# usbmidi.net
KiCad netlist of a schematic drawn in EAGLE
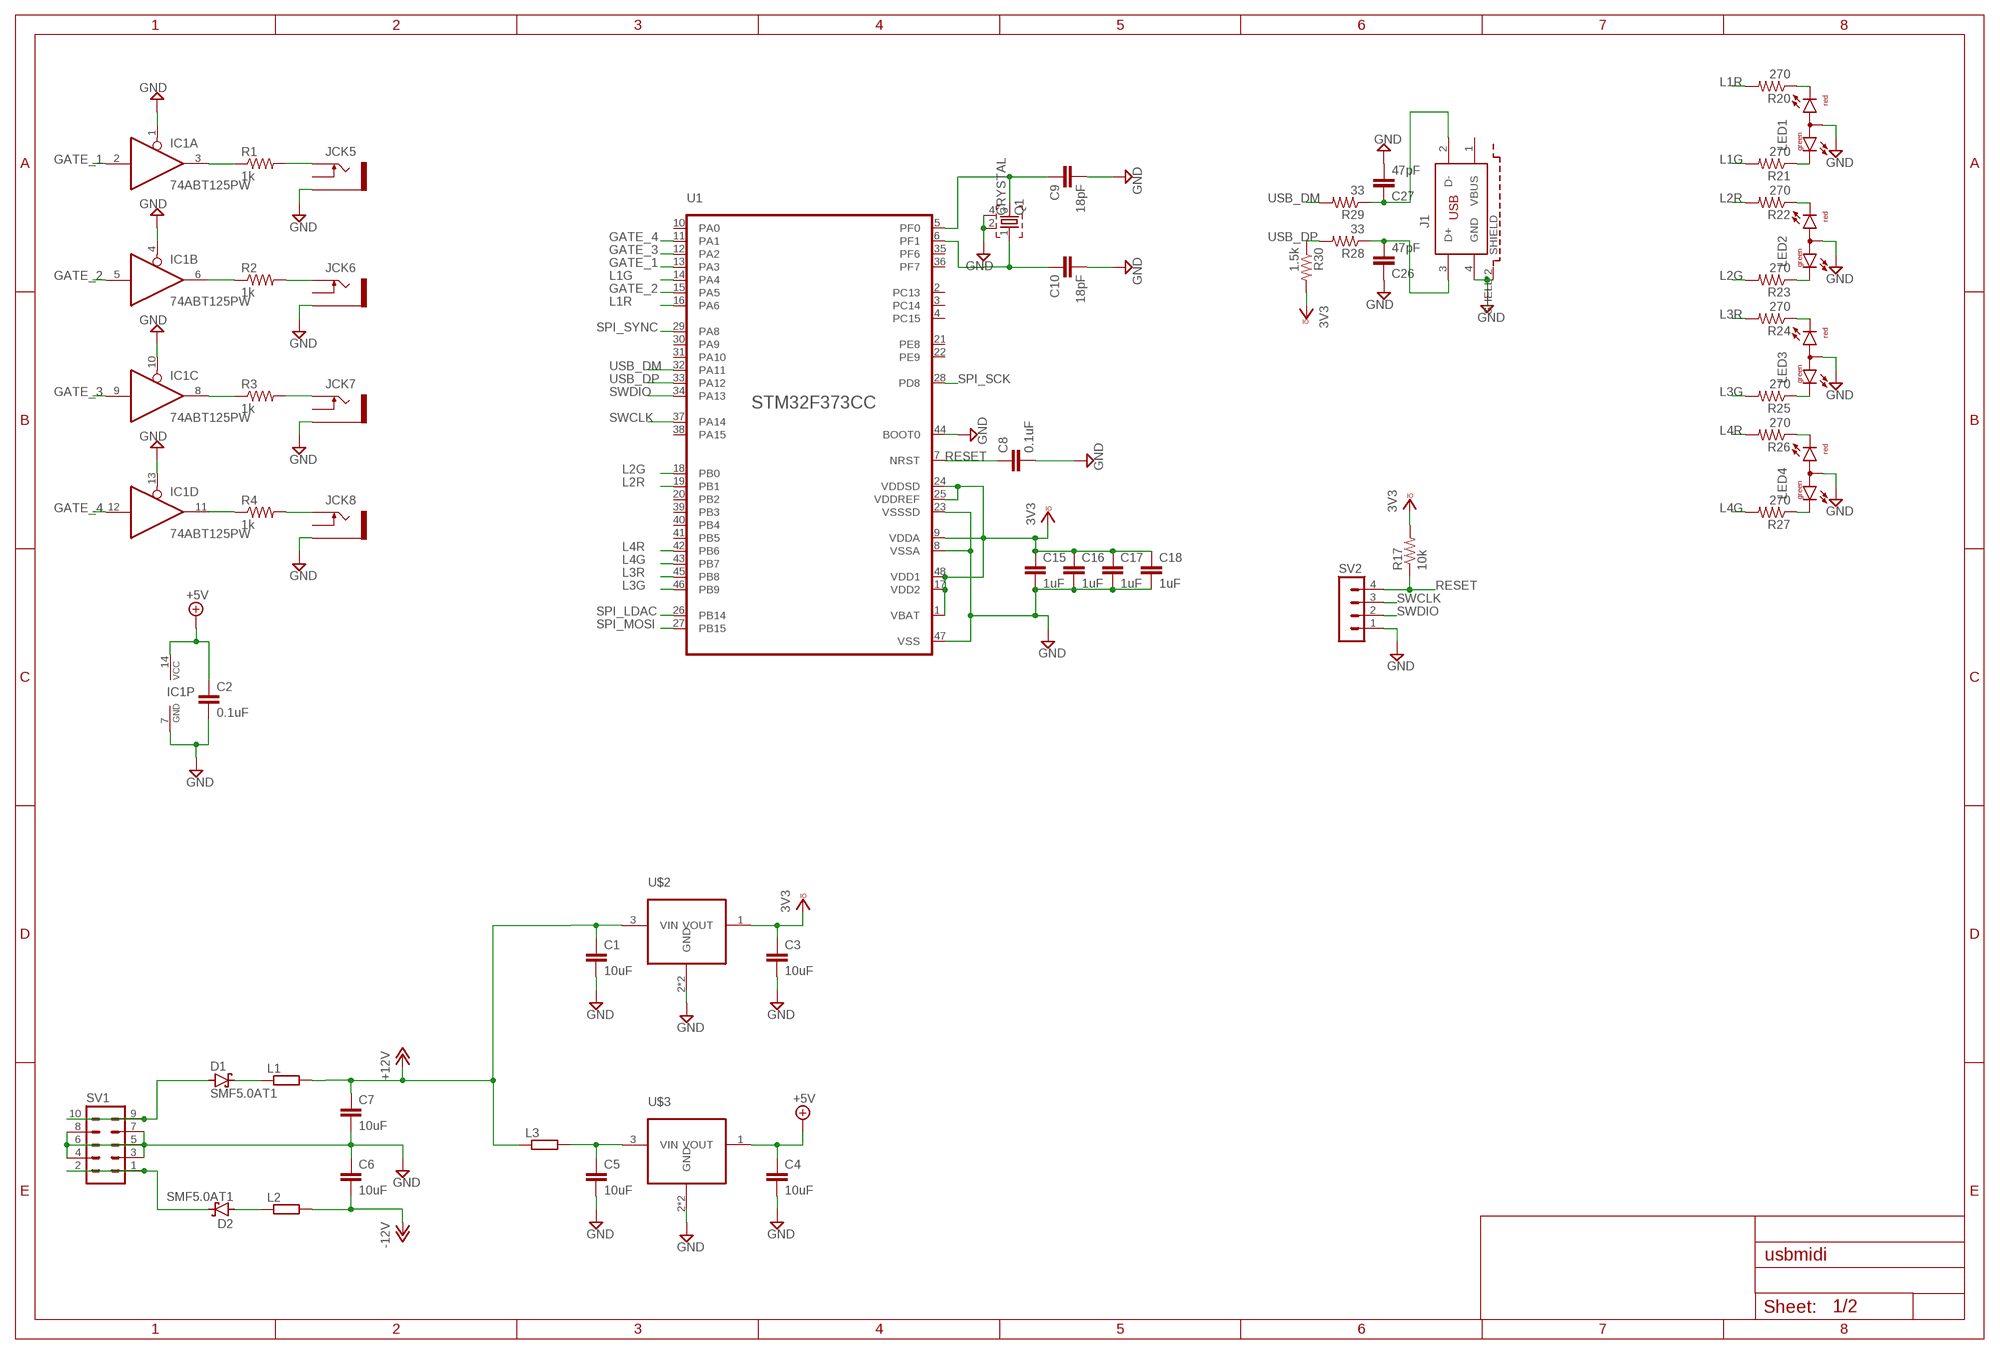
[diagram p0: schematic, sheet 1]
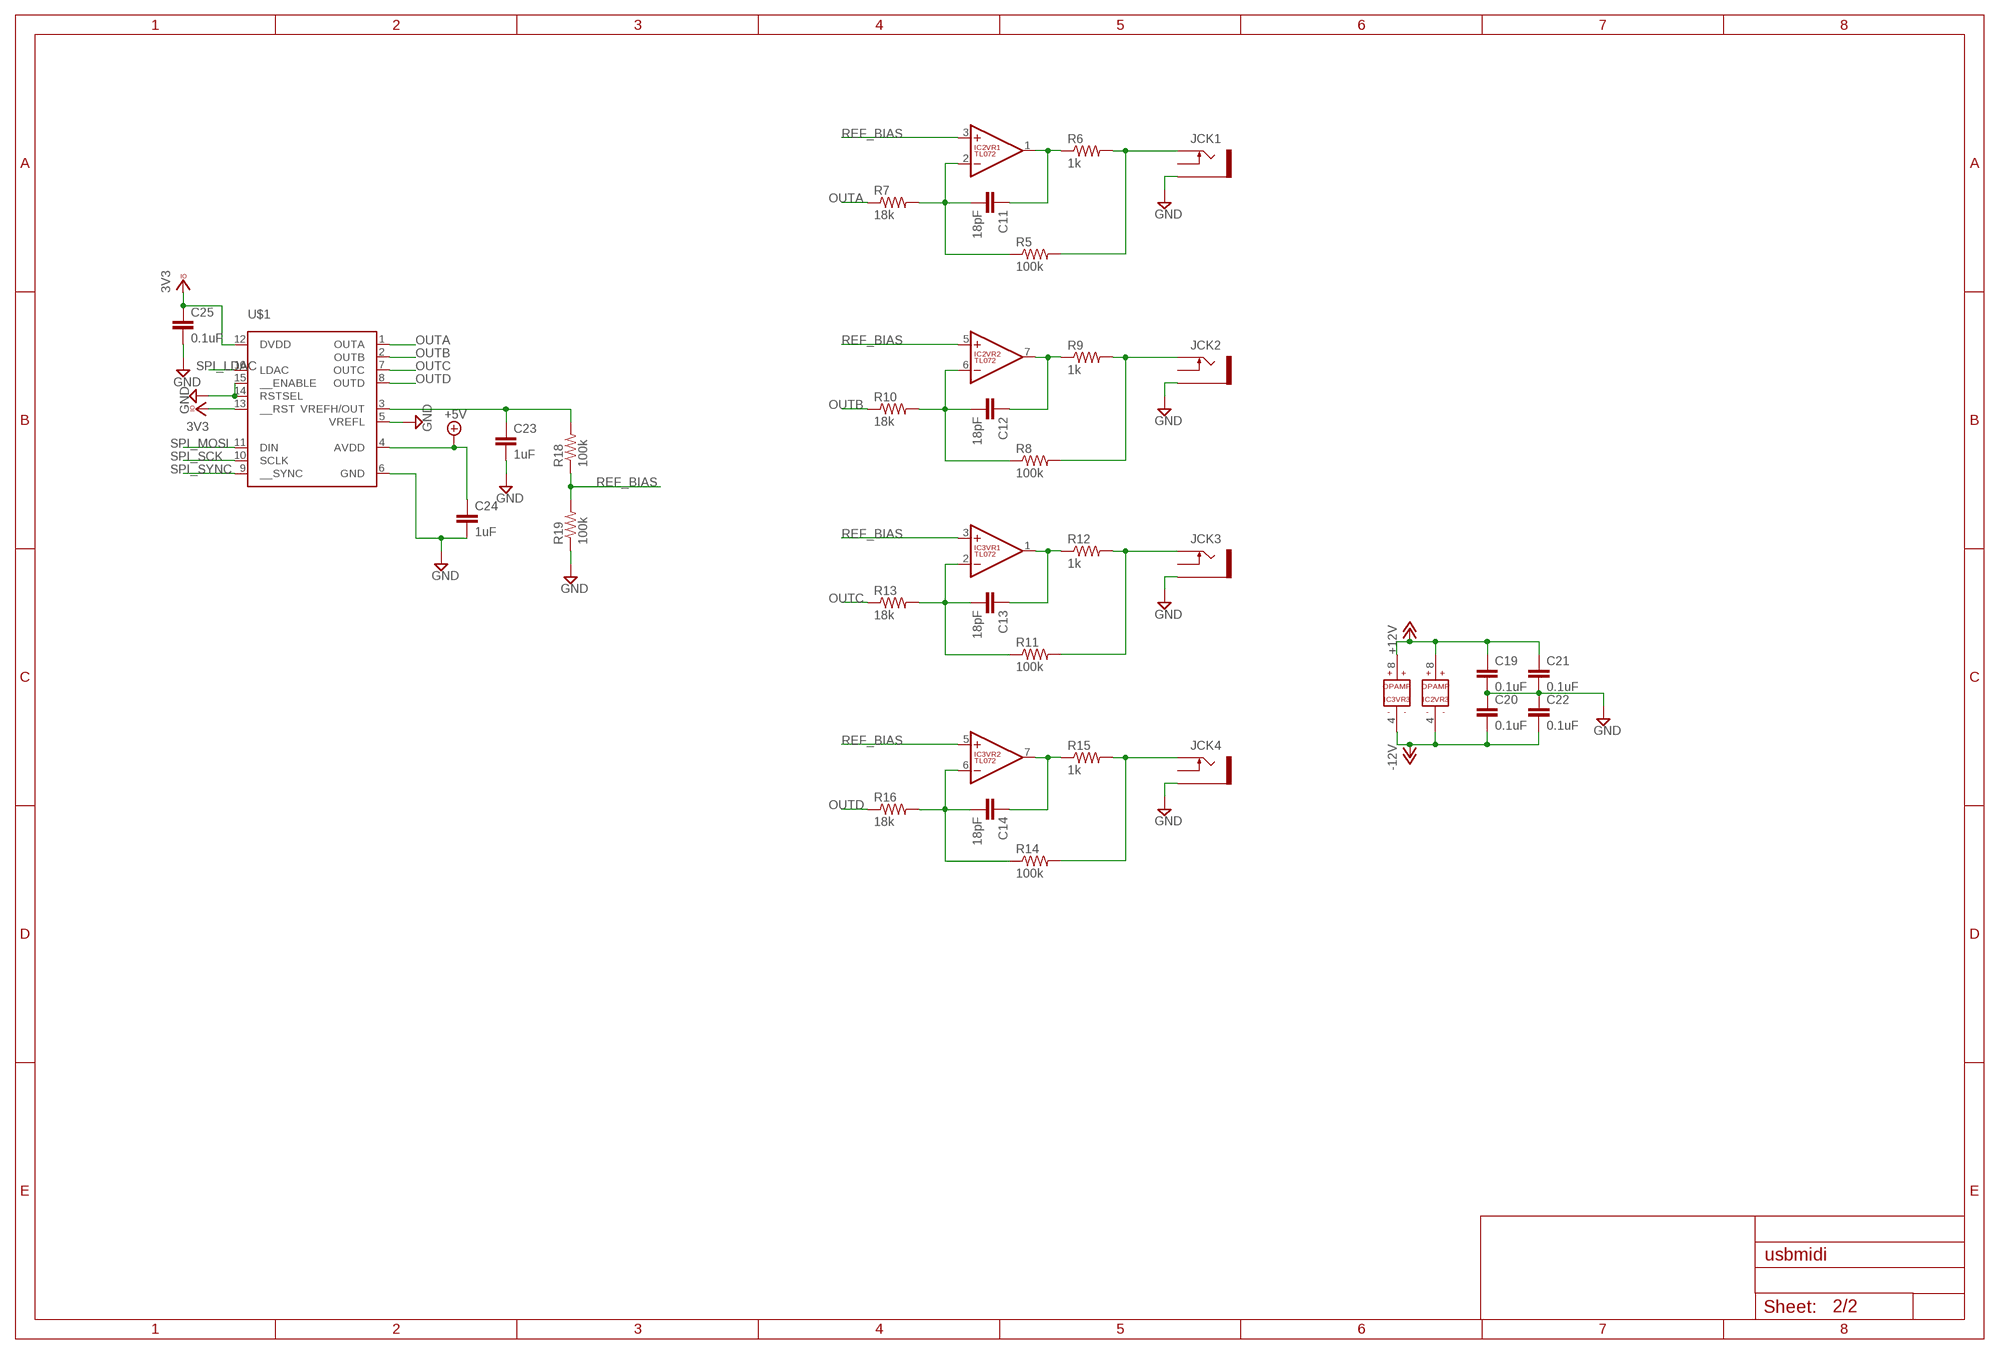
[diagram p1: schematic, sheet 2]

(export (version "E")
  (design (tool "Eeschema 10.0.6"))
  (components
    (comp (ref "C11")
      (value "18pF")
      (footprint "eagle-import:C0603K")
      (libsource (lib "eagle-import") (part "C-EUC0603K"))
    )
    (comp (ref "C12")
      (value "18pF")
      (footprint "eagle-import:C0603K")
      (libsource (lib "eagle-import") (part "C-EUC0603K"))
    )
    (comp (ref "C13")
      (value "18pF")
      (footprint "eagle-import:C0603K")
      (libsource (lib "eagle-import") (part "C-EUC0603K"))
    )
    (comp (ref "C14")
      (value "18pF")
      (footprint "eagle-import:C0603K")
      (libsource (lib "eagle-import") (part "C-EUC0603K"))
    )
    (comp (ref "C19")
      (value "0.1uF")
      (footprint "eagle-import:C0603K")
      (libsource (lib "eagle-import") (part "C-EUC0603K"))
    )
    (comp (ref "C20")
      (value "0.1uF")
      (footprint "eagle-import:C0603K")
      (libsource (lib "eagle-import") (part "C-EUC0603K"))
    )
    (comp (ref "C21")
      (value "0.1uF")
      (footprint "eagle-import:C0603K")
      (libsource (lib "eagle-import") (part "C-EUC0603K"))
    )
    (comp (ref "C22")
      (value "0.1uF")
      (footprint "eagle-import:C0603K")
      (libsource (lib "eagle-import") (part "C-EUC0603K"))
    )
    (comp (ref "C23")
      (value "1uF")
      (footprint "eagle-import:C0603K")
      (libsource (lib "eagle-import") (part "C-EUC0603K"))
    )
    (comp (ref "C24")
      (value "1uF")
      (footprint "eagle-import:C0603K")
      (libsource (lib "eagle-import") (part "C-EUC0603K"))
    )
    (comp (ref "C25")
      (value "0.1uF")
      (footprint "eagle-import:C0603K")
      (libsource (lib "eagle-import") (part "C-EUC0603K"))
    )
    (comp (ref "IC2")
      (value "TL072")
      (footprint "eagle-import:SO08")
      (libsource (lib "eagle-import") (part "TL072"))
    )
    (comp (ref "IC3")
      (value "TL072")
      (footprint "eagle-import:SO08")
      (libsource (lib "eagle-import") (part "TL072"))
    )
    (comp (ref "JCK1")
      (value "THONKICONNNEW")
      (footprint "eagle-import:WQP-PJ301M-12_JACK")
      (libsource (lib "eagle-import") (part "THONKICONNNEW"))
    )
    (comp (ref "JCK2")
      (value "THONKICONNNEW")
      (footprint "eagle-import:WQP-PJ301M-12_JACK")
      (libsource (lib "eagle-import") (part "THONKICONNNEW"))
    )
    (comp (ref "JCK3")
      (value "THONKICONNNEW")
      (footprint "eagle-import:WQP-PJ301M-12_JACK")
      (libsource (lib "eagle-import") (part "THONKICONNNEW"))
    )
    (comp (ref "JCK4")
      (value "THONKICONNNEW")
      (footprint "eagle-import:WQP-PJ301M-12_JACK")
      (libsource (lib "eagle-import") (part "THONKICONNNEW"))
    )
    (comp (ref "R5")
      (value "100k")
      (footprint "eagle-import:R0603")
      (libsource (lib "eagle-import") (part "R-US_R0603"))
    )
    (comp (ref "R6")
      (value "1k")
      (footprint "eagle-import:R0603")
      (libsource (lib "eagle-import") (part "R-US_R0603"))
    )
    (comp (ref "R7")
      (value "18k")
      (footprint "eagle-import:R0603")
      (libsource (lib "eagle-import") (part "R-US_R0603"))
    )
    (comp (ref "R8")
      (value "100k")
      (footprint "eagle-import:R0603")
      (libsource (lib "eagle-import") (part "R-US_R0603"))
    )
    (comp (ref "R9")
      (value "1k")
      (footprint "eagle-import:R0603")
      (libsource (lib "eagle-import") (part "R-US_R0603"))
    )
    (comp (ref "R10")
      (value "18k")
      (footprint "eagle-import:R0603")
      (libsource (lib "eagle-import") (part "R-US_R0603"))
    )
    (comp (ref "R11")
      (value "100k")
      (footprint "eagle-import:R0603")
      (libsource (lib "eagle-import") (part "R-US_R0603"))
    )
    (comp (ref "R12")
      (value "1k")
      (footprint "eagle-import:R0603")
      (libsource (lib "eagle-import") (part "R-US_R0603"))
    )
    (comp (ref "R13")
      (value "18k")
      (footprint "eagle-import:R0603")
      (libsource (lib "eagle-import") (part "R-US_R0603"))
    )
    (comp (ref "R14")
      (value "100k")
      (footprint "eagle-import:R0603")
      (libsource (lib "eagle-import") (part "R-US_R0603"))
    )
    (comp (ref "R15")
      (value "1k")
      (footprint "eagle-import:R0603")
      (libsource (lib "eagle-import") (part "R-US_R0603"))
    )
    (comp (ref "R16")
      (value "18k")
      (footprint "eagle-import:R0603")
      (libsource (lib "eagle-import") (part "R-US_R0603"))
    )
    (comp (ref "R18")
      (value "100k")
      (footprint "eagle-import:R0603")
      (libsource (lib "eagle-import") (part "R-US_R0603"))
    )
    (comp (ref "R19")
      (value "100k")
      (footprint "eagle-import:R0603")
      (libsource (lib "eagle-import") (part "R-US_R0603"))
    )
    (comp (ref "U$1")
      (value "DAC8565")
      (footprint "eagle-import:TSSOP16")
      (libsource (lib "eagle-import") (part "DAC8565"))
    )
    (comp (ref "C1")
      (value "10uF")
      (footprint "eagle-import:C0805")
      (libsource (lib "eagle-import") (part "C-EUC0805"))
    )
    (comp (ref "C2")
      (value "0.1uF")
      (footprint "eagle-import:C0603K")
      (libsource (lib "eagle-import") (part "C-EUC0603K"))
    )
    (comp (ref "C3")
      (value "10uF")
      (footprint "eagle-import:C0805")
      (libsource (lib "eagle-import") (part "C-EUC0805"))
    )
    (comp (ref "C4")
      (value "10uF")
      (footprint "eagle-import:C0805")
      (libsource (lib "eagle-import") (part "C-EUC0805"))
    )
    (comp (ref "C5")
      (value "10uF")
      (footprint "eagle-import:C0805")
      (libsource (lib "eagle-import") (part "C-EUC0805"))
    )
    (comp (ref "C6")
      (value "10uF")
      (footprint "eagle-import:C0805")
      (libsource (lib "eagle-import") (part "C-EUC0805"))
    )
    (comp (ref "C7")
      (value "10uF")
      (footprint "eagle-import:C0805")
      (libsource (lib "eagle-import") (part "C-EUC0805"))
    )
    (comp (ref "C8")
      (value "0.1uF")
      (footprint "eagle-import:C0603K")
      (libsource (lib "eagle-import") (part "C-EUC0603K"))
    )
    (comp (ref "C9")
      (value "18pF")
      (footprint "eagle-import:C0603K")
      (libsource (lib "eagle-import") (part "C-EUC0603K"))
    )
    (comp (ref "C10")
      (value "18pF")
      (footprint "eagle-import:C0603K")
      (libsource (lib "eagle-import") (part "C-EUC0603K"))
    )
    (comp (ref "C15")
      (value "1uF")
      (footprint "eagle-import:C0603K")
      (libsource (lib "eagle-import") (part "C-EUC0603K"))
    )
    (comp (ref "C16")
      (value "1uF")
      (footprint "eagle-import:C0603K")
      (libsource (lib "eagle-import") (part "C-EUC0603K"))
    )
    (comp (ref "C17")
      (value "1uF")
      (footprint "eagle-import:C0603K")
      (libsource (lib "eagle-import") (part "C-EUC0603K"))
    )
    (comp (ref "C18")
      (value "1uF")
      (footprint "eagle-import:C0603K")
      (libsource (lib "eagle-import") (part "C-EUC0603K"))
    )
    (comp (ref "C26")
      (value "47pF")
      (footprint "eagle-import:C0603K")
      (libsource (lib "eagle-import") (part "C-EUC0603K"))
    )
    (comp (ref "C27")
      (value "47pF")
      (footprint "eagle-import:C0603K")
      (libsource (lib "eagle-import") (part "C-EUC0603K"))
    )
    (comp (ref "D1")
      (value "SMF5.0AT1")
      (footprint "eagle-import:SOD123FL")
      (libsource (lib "eagle-import") (part "SMF5.0AT1"))
    )
    (comp (ref "D2")
      (value "SMF5.0AT1")
      (footprint "eagle-import:SOD123FL")
      (libsource (lib "eagle-import") (part "SMF5.0AT1"))
    )
    (comp (ref "IC1")
      (value "74ABT125PW")
      (footprint "eagle-import:TSSOP14")
      (libsource (lib "eagle-import") (part "74125PWABT"))
    )
    (comp (ref "J1")
      (value "61400413321")
      (footprint "eagle-import:61400413321")
      (libsource (lib "eagle-import") (part "61400413321"))
    )
    (comp (ref "JCK5")
      (value "THONKICONNNEW")
      (footprint "eagle-import:WQP-PJ301M-12_JACK")
      (libsource (lib "eagle-import") (part "THONKICONNNEW"))
    )
    (comp (ref "JCK6")
      (value "THONKICONNNEW")
      (footprint "eagle-import:WQP-PJ301M-12_JACK")
      (libsource (lib "eagle-import") (part "THONKICONNNEW"))
    )
    (comp (ref "JCK7")
      (value "THONKICONNNEW")
      (footprint "eagle-import:WQP-PJ301M-12_JACK")
      (libsource (lib "eagle-import") (part "THONKICONNNEW"))
    )
    (comp (ref "JCK8")
      (value "THONKICONNNEW")
      (footprint "eagle-import:WQP-PJ301M-12_JACK")
      (libsource (lib "eagle-import") (part "THONKICONNNEW"))
    )
    (comp (ref "L1")
      (value "R-EU_R0603")
      (footprint "eagle-import:R0603")
      (libsource (lib "eagle-import") (part "R-EU_R0603"))
    )
    (comp (ref "L2")
      (value "R-EU_R0603")
      (footprint "eagle-import:R0603")
      (libsource (lib "eagle-import") (part "R-EU_R0603"))
    )
    (comp (ref "L3")
      (value "R-EU_R0603")
      (footprint "eagle-import:R0603")
      (libsource (lib "eagle-import") (part "R-EU_R0603"))
    )
    (comp (ref "LED1")
      (value "L-115WEGW-CA")
      (footprint "eagle-import:DUOLED-A-3MM")
      (libsource (lib "eagle-import") (part "L-115WEGW-CA"))
    )
    (comp (ref "LED2")
      (value "L-115WEGW-CA")
      (footprint "eagle-import:DUOLED-A-3MM")
      (libsource (lib "eagle-import") (part "L-115WEGW-CA"))
    )
    (comp (ref "LED3")
      (value "L-115WEGW-CA")
      (footprint "eagle-import:DUOLED-A-3MM")
      (libsource (lib "eagle-import") (part "L-115WEGW-CA"))
    )
    (comp (ref "LED4")
      (value "L-115WEGW-CA")
      (footprint "eagle-import:DUOLED-A-3MM")
      (libsource (lib "eagle-import") (part "L-115WEGW-CA"))
    )
    (comp (ref "Q1")
      (value "CRYSTAL")
      (footprint "eagle-import:CTS406")
      (libsource (lib "eagle-import") (part "CRYSTAL"))
    )
    (comp (ref "R1")
      (value "1k")
      (footprint "eagle-import:R0603")
      (libsource (lib "eagle-import") (part "R-US_R0603"))
    )
    (comp (ref "R2")
      (value "1k")
      (footprint "eagle-import:R0603")
      (libsource (lib "eagle-import") (part "R-US_R0603"))
    )
    (comp (ref "R3")
      (value "1k")
      (footprint "eagle-import:R0603")
      (libsource (lib "eagle-import") (part "R-US_R0603"))
    )
    (comp (ref "R4")
      (value "1k")
      (footprint "eagle-import:R0603")
      (libsource (lib "eagle-import") (part "R-US_R0603"))
    )
    (comp (ref "R17")
      (value "10k")
      (footprint "eagle-import:R0603")
      (libsource (lib "eagle-import") (part "R-US_R0603"))
    )
    (comp (ref "R20")
      (value "270")
      (footprint "eagle-import:R0603")
      (libsource (lib "eagle-import") (part "R-US_R0603"))
    )
    (comp (ref "R21")
      (value "270")
      (footprint "eagle-import:R0603")
      (libsource (lib "eagle-import") (part "R-US_R0603"))
    )
    (comp (ref "R22")
      (value "270")
      (footprint "eagle-import:R0603")
      (libsource (lib "eagle-import") (part "R-US_R0603"))
    )
    (comp (ref "R23")
      (value "270")
      (footprint "eagle-import:R0603")
      (libsource (lib "eagle-import") (part "R-US_R0603"))
    )
    (comp (ref "R24")
      (value "270")
      (footprint "eagle-import:R0603")
      (libsource (lib "eagle-import") (part "R-US_R0603"))
    )
    (comp (ref "R25")
      (value "270")
      (footprint "eagle-import:R0603")
      (libsource (lib "eagle-import") (part "R-US_R0603"))
    )
    (comp (ref "R26")
      (value "270")
      (footprint "eagle-import:R0603")
      (libsource (lib "eagle-import") (part "R-US_R0603"))
    )
    (comp (ref "R27")
      (value "270")
      (footprint "eagle-import:R0603")
      (libsource (lib "eagle-import") (part "R-US_R0603"))
    )
    (comp (ref "R28")
      (value "33")
      (footprint "eagle-import:R0603")
      (libsource (lib "eagle-import") (part "R-US_R0603"))
    )
    (comp (ref "R29")
      (value "33")
      (footprint "eagle-import:R0603")
      (libsource (lib "eagle-import") (part "R-US_R0603"))
    )
    (comp (ref "R30")
      (value "1.5k")
      (footprint "eagle-import:R0603")
      (libsource (lib "eagle-import") (part "R-US_R0603"))
    )
    (comp (ref "SV1")
      (value "MA05-2")
      (footprint "eagle-import:MA05-2")
      (libsource (lib "eagle-import") (part "MA05-2"))
    )
    (comp (ref "SV2")
      (value "MA04-1")
      (footprint "eagle-import:MA04-1")
      (libsource (lib "eagle-import") (part "MA04-1"))
    )
    (comp (ref "U$2")
      (value "LD2981ABUSOT89")
      (footprint "eagle-import:SOT89")
      (libsource (lib "eagle-import") (part "LD2981ABUSOT89"))
    )
    (comp (ref "U$3")
      (value "LD2981ABUSOT89")
      (footprint "eagle-import:SOT89")
      (libsource (lib "eagle-import") (part "LD2981ABUSOT89"))
    )
    (comp (ref "U1")
      (value "STM32F373LQFP48")
      (footprint "eagle-import:LQFP48")
      (libsource (lib "eagle-import") (part "STM32F373LQFP48"))
    )
  )
  (nets
    (net (code "1") (name "+5V") (class "Default")
      (node (ref "C2") (pin "1") (pinfunction "1_1") (pintype "passive"))
      (node (ref "C24") (pin "1") (pinfunction "1_1") (pintype "passive"))
      (node (ref "C4") (pin "1") (pinfunction "1_1") (pintype "passive"))
      (node (ref "IC1") (pin "14") (pinfunction "VCC_14") (pintype "power_in"))
      (node (ref "U$1") (pin "4") (pinfunction "AVDD_4") (pintype "bidirectional"))
      (node (ref "U$3") (pin "1") (pinfunction "VOUT_1") (pintype "bidirectional"))
    )
    (net (code "2") (name "+12V") (class "Default")
      (node (ref "C1") (pin "1") (pinfunction "1_1") (pintype "passive"))
      (node (ref "C19") (pin "1") (pinfunction "1_1") (pintype "passive"))
      (node (ref "C21") (pin "1") (pinfunction "1_1") (pintype "passive"))
      (node (ref "C7") (pin "1") (pinfunction "1_1") (pintype "passive"))
      (node (ref "IC2") (pin "8") (pinfunction "V+_8") (pintype "power_in"))
      (node (ref "IC3") (pin "8") (pinfunction "V+_8") (pintype "power_in"))
      (node (ref "L1") (pin "2") (pinfunction "2_2") (pintype "passive"))
      (node (ref "L3") (pin "1") (pinfunction "1_1") (pintype "passive"))
      (node (ref "U$2") (pin "3") (pinfunction "VIN_3") (pintype "bidirectional"))
    )
    (net (code "3") (name "-12V") (class "Default")
      (node (ref "C20") (pin "2") (pinfunction "2_2") (pintype "passive"))
      (node (ref "C22") (pin "2") (pinfunction "2_2") (pintype "passive"))
      (node (ref "C6") (pin "2") (pinfunction "2_2") (pintype "passive"))
      (node (ref "IC2") (pin "4") (pinfunction "V-_4") (pintype "power_in"))
      (node (ref "IC3") (pin "4") (pinfunction "V-_4") (pintype "power_in"))
      (node (ref "L2") (pin "2") (pinfunction "2_2") (pintype "passive"))
    )
    (net (code "4") (name "GATE_1") (class "Default")
      (node (ref "IC1") (pin "2") (pinfunction "I_2") (pintype "input"))
      (node (ref "U1") (pin "13") (pinfunction "PA3_13") (pintype "bidirectional"))
    )
    (net (code "5") (name "GATE_2") (class "Default")
      (node (ref "IC1") (pin "5") (pinfunction "I_5") (pintype "input"))
      (node (ref "U1") (pin "15") (pinfunction "PA5_15") (pintype "bidirectional"))
    )
    (net (code "6") (name "GATE_3") (class "Default")
      (node (ref "IC1") (pin "9") (pinfunction "I_9") (pintype "input"))
      (node (ref "U1") (pin "12") (pinfunction "PA2_12") (pintype "bidirectional"))
    )
    (net (code "7") (name "GATE_4") (class "Default")
      (node (ref "IC1") (pin "12") (pinfunction "I_12") (pintype "input"))
      (node (ref "U1") (pin "11") (pinfunction "PA1_11") (pintype "bidirectional"))
    )
    (net (code "8") (name "GND") (class "Default")
      (node (ref "C1") (pin "2") (pinfunction "2_2") (pintype "passive"))
      (node (ref "C10") (pin "2") (pinfunction "2_2") (pintype "passive"))
      (node (ref "C15") (pin "2") (pinfunction "2_2") (pintype "passive"))
      (node (ref "C16") (pin "2") (pinfunction "2_2") (pintype "passive"))
      (node (ref "C17") (pin "2") (pinfunction "2_2") (pintype "passive"))
      (node (ref "C18") (pin "2") (pinfunction "2_2") (pintype "passive"))
      (node (ref "C19") (pin "2") (pinfunction "2_2") (pintype "passive"))
      (node (ref "C2") (pin "2") (pinfunction "2_2") (pintype "passive"))
      (node (ref "C20") (pin "1") (pinfunction "1_1") (pintype "passive"))
      (node (ref "C21") (pin "2") (pinfunction "2_2") (pintype "passive"))
      (node (ref "C22") (pin "1") (pinfunction "1_1") (pintype "passive"))
      (node (ref "C23") (pin "2") (pinfunction "2_2") (pintype "passive"))
      (node (ref "C24") (pin "2") (pinfunction "2_2") (pintype "passive"))
      (node (ref "C25") (pin "2") (pinfunction "2_2") (pintype "passive"))
      (node (ref "C26") (pin "1") (pinfunction "1_1") (pintype "passive"))
      (node (ref "C27") (pin "2") (pinfunction "2_2") (pintype "passive"))
      (node (ref "C3") (pin "2") (pinfunction "2_2") (pintype "passive"))
      (node (ref "C4") (pin "2") (pinfunction "2_2") (pintype "passive"))
      (node (ref "C5") (pin "2") (pinfunction "2_2") (pintype "passive"))
      (node (ref "C6") (pin "1") (pinfunction "1_1") (pintype "passive"))
      (node (ref "C7") (pin "2") (pinfunction "2_2") (pintype "passive"))
      (node (ref "C8") (pin "2") (pinfunction "2_2") (pintype "passive"))
      (node (ref "C9") (pin "2") (pinfunction "2_2") (pintype "passive"))
      (node (ref "IC1") (pin "1") (pinfunction "OE_1") (pintype "input"))
      (node (ref "IC1") (pin "10") (pinfunction "OE_10") (pintype "input"))
      (node (ref "IC1") (pin "13") (pinfunction "OE_13") (pintype "input"))
      (node (ref "IC1") (pin "4") (pinfunction "OE_4") (pintype "input"))
      (node (ref "IC1") (pin "7") (pinfunction "GND_7") (pintype "power_in"))
      (node (ref "J1") (pin "4") (pinfunction "GND_4") (pintype "bidirectional"))
      (node (ref "J1") (pin "SHELL") (pinfunction "SHIELD_SHELL") (pintype "bidirectional"))
      (node (ref "J1") (pin "SHELL1") (pinfunction "SHIELD_SHELL1") (pintype "bidirectional"))
      (node (ref "JCK1") (pin "P$3_SLEEVE") (pinfunction "SLEEVE_P$3_SLEEVE") (pintype "passive"))
      (node (ref "JCK2") (pin "P$3_SLEEVE") (pinfunction "SLEEVE_P$3_SLEEVE") (pintype "passive"))
      (node (ref "JCK3") (pin "P$3_SLEEVE") (pinfunction "SLEEVE_P$3_SLEEVE") (pintype "passive"))
      (node (ref "JCK4") (pin "P$3_SLEEVE") (pinfunction "SLEEVE_P$3_SLEEVE") (pintype "passive"))
      (node (ref "JCK5") (pin "P$3_SLEEVE") (pinfunction "SLEEVE_P$3_SLEEVE") (pintype "passive"))
      (node (ref "JCK6") (pin "P$3_SLEEVE") (pinfunction "SLEEVE_P$3_SLEEVE") (pintype "passive"))
      (node (ref "JCK7") (pin "P$3_SLEEVE") (pinfunction "SLEEVE_P$3_SLEEVE") (pintype "passive"))
      (node (ref "JCK8") (pin "P$3_SLEEVE") (pinfunction "SLEEVE_P$3_SLEEVE") (pintype "passive"))
      (node (ref "LED1") (pin "2") (pinfunction "A_2") (pintype "passive"))
      (node (ref "LED2") (pin "2") (pinfunction "A_2") (pintype "passive"))
      (node (ref "LED3") (pin "2") (pinfunction "A_2") (pintype "passive"))
      (node (ref "LED4") (pin "2") (pinfunction "A_2") (pintype "passive"))
      (node (ref "Q1") (pin "2") (pinfunction "2_2") (pintype "passive"))
      (node (ref "Q1") (pin "4") (pinfunction "4_4") (pintype "passive"))
      (node (ref "R19") (pin "1") (pinfunction "1_1") (pintype "passive"))
      (node (ref "SV1") (pin "3") (pinfunction "3_3") (pintype "passive"))
      (node (ref "SV1") (pin "4") (pinfunction "4_4") (pintype "passive"))
      (node (ref "SV1") (pin "5") (pinfunction "5_5") (pintype "passive"))
      (node (ref "SV1") (pin "6") (pinfunction "6_6") (pintype "passive"))
      (node (ref "SV1") (pin "7") (pinfunction "7_7") (pintype "passive"))
      (node (ref "SV1") (pin "8") (pinfunction "8_8") (pintype "passive"))
      (node (ref "SV2") (pin "1") (pinfunction "1_1") (pintype "passive"))
      (node (ref "U$1") (pin "14") (pinfunction "RSTSEL_14") (pintype "bidirectional"))
      (node (ref "U$1") (pin "15") (pinfunction "__ENABLE_15") (pintype "bidirectional"))
      (node (ref "U$1") (pin "5") (pinfunction "VREFL_5") (pintype "bidirectional"))
      (node (ref "U$1") (pin "6") (pinfunction "GND_6") (pintype "bidirectional"))
      (node (ref "U$2") (pin "2") (pinfunction "GND_2") (pintype "bidirectional"))
      (node (ref "U$2") (pin "2@1") (pinfunction "GND_2@1") (pintype "bidirectional"))
      (node (ref "U$3") (pin "2") (pinfunction "GND_2") (pintype "bidirectional"))
      (node (ref "U$3") (pin "2@1") (pinfunction "GND_2@1") (pintype "bidirectional"))
      (node (ref "U1") (pin "23") (pinfunction "VSSSD_23") (pintype "bidirectional"))
      (node (ref "U1") (pin "44") (pinfunction "BOOT0_44") (pintype "bidirectional"))
      (node (ref "U1") (pin "47") (pinfunction "VSS_47") (pintype "bidirectional"))
      (node (ref "U1") (pin "8") (pinfunction "VSSA_8") (pintype "bidirectional"))
    )
    (net (code "9") (name "L1G") (class "Default")
      (node (ref "R21") (pin "2") (pinfunction "2_2") (pintype "passive"))
      (node (ref "U1") (pin "14") (pinfunction "PA4_14") (pintype "bidirectional"))
    )
    (net (code "10") (name "L1R") (class "Default")
      (node (ref "R20") (pin "2") (pinfunction "2_2") (pintype "passive"))
      (node (ref "U1") (pin "16") (pinfunction "PA6_16") (pintype "bidirectional"))
    )
    (net (code "11") (name "L2G") (class "Default")
      (node (ref "R23") (pin "2") (pinfunction "2_2") (pintype "passive"))
      (node (ref "U1") (pin "18") (pinfunction "PB0_18") (pintype "bidirectional"))
    )
    (net (code "12") (name "L2R") (class "Default")
      (node (ref "R22") (pin "2") (pinfunction "2_2") (pintype "passive"))
      (node (ref "U1") (pin "19") (pinfunction "PB1_19") (pintype "bidirectional"))
    )
    (net (code "13") (name "L3G") (class "Default")
      (node (ref "R25") (pin "2") (pinfunction "2_2") (pintype "passive"))
      (node (ref "U1") (pin "46") (pinfunction "PB9_46") (pintype "bidirectional"))
    )
    (net (code "14") (name "L3R") (class "Default")
      (node (ref "R24") (pin "2") (pinfunction "2_2") (pintype "passive"))
      (node (ref "U1") (pin "45") (pinfunction "PB8_45") (pintype "bidirectional"))
    )
    (net (code "15") (name "L4G") (class "Default")
      (node (ref "R27") (pin "2") (pinfunction "2_2") (pintype "passive"))
      (node (ref "U1") (pin "43") (pinfunction "PB7_43") (pintype "bidirectional"))
    )
    (net (code "16") (name "L4R") (class "Default")
      (node (ref "R26") (pin "2") (pinfunction "2_2") (pintype "passive"))
      (node (ref "U1") (pin "42") (pinfunction "PB6_42") (pintype "bidirectional"))
    )
    (net (code "17") (name "Net-(D1-PadA)") (class "Default")
      (node (ref "D1") (pin "A") (pinfunction "A_A") (pintype "passive"))
      (node (ref "SV1") (pin "10") (pinfunction "10_10") (pintype "passive"))
      (node (ref "SV1") (pin "9") (pinfunction "9_9") (pintype "passive"))
    )
    (net (code "18") (name "Net-(D1-PadC)") (class "Default")
      (node (ref "D1") (pin "C") (pinfunction "C_C") (pintype "passive"))
      (node (ref "L1") (pin "1") (pinfunction "1_1") (pintype "passive"))
    )
    (net (code "19") (name "Net-(D2-PadA)") (class "Default")
      (node (ref "D2") (pin "A") (pinfunction "A_A") (pintype "passive"))
      (node (ref "L2") (pin "1") (pinfunction "1_1") (pintype "passive"))
    )
    (net (code "20") (name "Net-(D2-PadC)") (class "Default")
      (node (ref "D2") (pin "C") (pinfunction "C_C") (pintype "passive"))
      (node (ref "SV1") (pin "1") (pinfunction "1_1") (pintype "passive"))
      (node (ref "SV1") (pin "2") (pinfunction "2_2") (pintype "passive"))
    )
    (net (code "21") (name "Net-(IC1A-O)") (class "Default")
      (node (ref "IC1") (pin "3") (pinfunction "O_3") (pintype "tri_state"))
      (node (ref "R1") (pin "1") (pinfunction "1_1") (pintype "passive"))
    )
    (net (code "22") (name "Net-(IC1B-O)") (class "Default")
      (node (ref "IC1") (pin "6") (pinfunction "O_6") (pintype "tri_state"))
      (node (ref "R2") (pin "1") (pinfunction "1_1") (pintype "passive"))
    )
    (net (code "23") (name "Net-(IC1C-O)") (class "Default")
      (node (ref "IC1") (pin "8") (pinfunction "O_8") (pintype "tri_state"))
      (node (ref "R3") (pin "1") (pinfunction "1_1") (pintype "passive"))
    )
    (net (code "24") (name "Net-(IC1D-O)") (class "Default")
      (node (ref "IC1") (pin "11") (pinfunction "O_11") (pintype "tri_state"))
      (node (ref "R4") (pin "1") (pinfunction "1_1") (pintype "passive"))
    )
    (net (code "25") (name "Net-(IC2A--IN)") (class "Default")
      (node (ref "C11") (pin "2") (pinfunction "2_2") (pintype "passive"))
      (node (ref "IC2") (pin "2") (pinfunction "-IN_2") (pintype "input"))
      (node (ref "R5") (pin "1") (pinfunction "1_1") (pintype "passive"))
      (node (ref "R7") (pin "2") (pinfunction "2_2") (pintype "passive"))
    )
    (net (code "26") (name "Net-(IC2A-OUT)") (class "Default")
      (node (ref "C11") (pin "1") (pinfunction "1_1") (pintype "passive"))
      (node (ref "IC2") (pin "1") (pinfunction "OUT_1") (pintype "output"))
      (node (ref "R6") (pin "1") (pinfunction "1_1") (pintype "passive"))
    )
    (net (code "27") (name "Net-(IC2B--IN)") (class "Default")
      (node (ref "C12") (pin "2") (pinfunction "2_2") (pintype "passive"))
      (node (ref "IC2") (pin "6") (pinfunction "-IN_6") (pintype "input"))
      (node (ref "R10") (pin "2") (pinfunction "2_2") (pintype "passive"))
      (node (ref "R8") (pin "1") (pinfunction "1_1") (pintype "passive"))
    )
    (net (code "28") (name "Net-(IC2B-OUT)") (class "Default")
      (node (ref "C12") (pin "1") (pinfunction "1_1") (pintype "passive"))
      (node (ref "IC2") (pin "7") (pinfunction "OUT_7") (pintype "output"))
      (node (ref "R9") (pin "1") (pinfunction "1_1") (pintype "passive"))
    )
    (net (code "29") (name "Net-(IC3A--IN)") (class "Default")
      (node (ref "C13") (pin "2") (pinfunction "2_2") (pintype "passive"))
      (node (ref "IC3") (pin "2") (pinfunction "-IN_2") (pintype "input"))
      (node (ref "R11") (pin "1") (pinfunction "1_1") (pintype "passive"))
      (node (ref "R13") (pin "2") (pinfunction "2_2") (pintype "passive"))
    )
    (net (code "30") (name "Net-(IC3A-OUT)") (class "Default")
      (node (ref "C13") (pin "1") (pinfunction "1_1") (pintype "passive"))
      (node (ref "IC3") (pin "1") (pinfunction "OUT_1") (pintype "output"))
      (node (ref "R12") (pin "1") (pinfunction "1_1") (pintype "passive"))
    )
    (net (code "31") (name "Net-(IC3B--IN)") (class "Default")
      (node (ref "C14") (pin "2") (pinfunction "2_2") (pintype "passive"))
      (node (ref "IC3") (pin "6") (pinfunction "-IN_6") (pintype "input"))
      (node (ref "R14") (pin "1") (pinfunction "1_1") (pintype "passive"))
      (node (ref "R16") (pin "2") (pinfunction "2_2") (pintype "passive"))
    )
    (net (code "32") (name "Net-(IC3B-OUT)") (class "Default")
      (node (ref "C14") (pin "1") (pinfunction "1_1") (pintype "passive"))
      (node (ref "IC3") (pin "7") (pinfunction "OUT_7") (pintype "output"))
      (node (ref "R15") (pin "1") (pinfunction "1_1") (pintype "passive"))
    )
    (net (code "33") (name "Net-(J1-D+)") (class "Default")
      (node (ref "C26") (pin "2") (pinfunction "2_2") (pintype "passive"))
      (node (ref "J1") (pin "3") (pinfunction "D+_3") (pintype "bidirectional"))
      (node (ref "R28") (pin "1") (pinfunction "1_1") (pintype "passive"))
    )
    (net (code "34") (name "Net-(J1-D-)") (class "Default")
      (node (ref "C27") (pin "1") (pinfunction "1_1") (pintype "passive"))
      (node (ref "J1") (pin "2") (pinfunction "D-_2") (pintype "bidirectional"))
      (node (ref "R29") (pin "1") (pinfunction "1_1") (pintype "passive"))
    )
    (net (code "35") (name "Net-(JCK1-TIP)") (class "Default")
      (node (ref "JCK1") (pin "P$1_TIP") (pinfunction "TIP_P$1_TIP") (pintype "passive"))
      (node (ref "R5") (pin "2") (pinfunction "2_2") (pintype "passive"))
      (node (ref "R6") (pin "2") (pinfunction "2_2") (pintype "passive"))
    )
    (net (code "36") (name "Net-(JCK2-TIP)") (class "Default")
      (node (ref "JCK2") (pin "P$1_TIP") (pinfunction "TIP_P$1_TIP") (pintype "passive"))
      (node (ref "R8") (pin "2") (pinfunction "2_2") (pintype "passive"))
      (node (ref "R9") (pin "2") (pinfunction "2_2") (pintype "passive"))
    )
    (net (code "37") (name "Net-(JCK3-TIP)") (class "Default")
      (node (ref "JCK3") (pin "P$1_TIP") (pinfunction "TIP_P$1_TIP") (pintype "passive"))
      (node (ref "R11") (pin "2") (pinfunction "2_2") (pintype "passive"))
      (node (ref "R12") (pin "2") (pinfunction "2_2") (pintype "passive"))
    )
    (net (code "38") (name "Net-(JCK4-TIP)") (class "Default")
      (node (ref "JCK4") (pin "P$1_TIP") (pinfunction "TIP_P$1_TIP") (pintype "passive"))
      (node (ref "R14") (pin "2") (pinfunction "2_2") (pintype "passive"))
      (node (ref "R15") (pin "2") (pinfunction "2_2") (pintype "passive"))
    )
    (net (code "39") (name "Net-(JCK5-TIP)") (class "Default")
      (node (ref "JCK5") (pin "P$1_TIP") (pinfunction "TIP_P$1_TIP") (pintype "passive"))
      (node (ref "R1") (pin "2") (pinfunction "2_2") (pintype "passive"))
    )
    (net (code "40") (name "Net-(JCK6-TIP)") (class "Default")
      (node (ref "JCK6") (pin "P$1_TIP") (pinfunction "TIP_P$1_TIP") (pintype "passive"))
      (node (ref "R2") (pin "2") (pinfunction "2_2") (pintype "passive"))
    )
    (net (code "41") (name "Net-(JCK7-TIP)") (class "Default")
      (node (ref "JCK7") (pin "P$1_TIP") (pinfunction "TIP_P$1_TIP") (pintype "passive"))
      (node (ref "R3") (pin "2") (pinfunction "2_2") (pintype "passive"))
    )
    (net (code "42") (name "Net-(JCK8-TIP)") (class "Default")
      (node (ref "JCK8") (pin "P$1_TIP") (pinfunction "TIP_P$1_TIP") (pintype "passive"))
      (node (ref "R4") (pin "2") (pinfunction "2_2") (pintype "passive"))
    )
    (net (code "43") (name "Net-(LED1-CG)") (class "Default")
      (node (ref "LED1") (pin "1") (pinfunction "CG_1") (pintype "passive"))
      (node (ref "R21") (pin "1") (pinfunction "1_1") (pintype "passive"))
    )
    (net (code "44") (name "Net-(LED1-CR)") (class "Default")
      (node (ref "LED1") (pin "3") (pinfunction "CR_3") (pintype "passive"))
      (node (ref "R20") (pin "1") (pinfunction "1_1") (pintype "passive"))
    )
    (net (code "45") (name "Net-(LED2-CG)") (class "Default")
      (node (ref "LED2") (pin "1") (pinfunction "CG_1") (pintype "passive"))
      (node (ref "R23") (pin "1") (pinfunction "1_1") (pintype "passive"))
    )
    (net (code "46") (name "Net-(LED2-CR)") (class "Default")
      (node (ref "LED2") (pin "3") (pinfunction "CR_3") (pintype "passive"))
      (node (ref "R22") (pin "1") (pinfunction "1_1") (pintype "passive"))
    )
    (net (code "47") (name "Net-(LED3-CG)") (class "Default")
      (node (ref "LED3") (pin "1") (pinfunction "CG_1") (pintype "passive"))
      (node (ref "R25") (pin "1") (pinfunction "1_1") (pintype "passive"))
    )
    (net (code "48") (name "Net-(LED3-CR)") (class "Default")
      (node (ref "LED3") (pin "3") (pinfunction "CR_3") (pintype "passive"))
      (node (ref "R24") (pin "1") (pinfunction "1_1") (pintype "passive"))
    )
    (net (code "49") (name "Net-(LED4-CG)") (class "Default")
      (node (ref "LED4") (pin "1") (pinfunction "CG_1") (pintype "passive"))
      (node (ref "R27") (pin "1") (pinfunction "1_1") (pintype "passive"))
    )
    (net (code "50") (name "Net-(LED4-CR)") (class "Default")
      (node (ref "LED4") (pin "3") (pinfunction "CR_3") (pintype "passive"))
      (node (ref "R26") (pin "1") (pinfunction "1_1") (pintype "passive"))
    )
    (net (code "51") (name "Net-(U$1-VREFH{slash}OUT)") (class "Default")
      (node (ref "C23") (pin "1") (pinfunction "1_1") (pintype "passive"))
      (node (ref "R18") (pin "2") (pinfunction "2_2") (pintype "passive"))
      (node (ref "U$1") (pin "3") (pinfunction "VREFH/OUT_3") (pintype "bidirectional"))
    )
    (net (code "52") (name "Net-(U$3-VIN)") (class "Default")
      (node (ref "C5") (pin "1") (pinfunction "1_1") (pintype "passive"))
      (node (ref "L3") (pin "2") (pinfunction "2_2") (pintype "passive"))
      (node (ref "U$3") (pin "3") (pinfunction "VIN_3") (pintype "bidirectional"))
    )
    (net (code "53") (name "Net-(U1-PF0)") (class "Default")
      (node (ref "C9") (pin "1") (pinfunction "1_1") (pintype "passive"))
      (node (ref "Q1") (pin "3") (pinfunction "3_3") (pintype "passive"))
      (node (ref "U1") (pin "5") (pinfunction "PF0_5") (pintype "bidirectional"))
    )
    (net (code "54") (name "Net-(U1-PF1)") (class "Default")
      (node (ref "C10") (pin "1") (pinfunction "1_1") (pintype "passive"))
      (node (ref "Q1") (pin "1") (pinfunction "1_1") (pintype "passive"))
      (node (ref "U1") (pin "6") (pinfunction "PF1_6") (pintype "bidirectional"))
    )
    (net (code "55") (name "OUTA") (class "Default")
      (node (ref "R7") (pin "1") (pinfunction "1_1") (pintype "passive"))
      (node (ref "U$1") (pin "1") (pinfunction "OUTA_1") (pintype "bidirectional"))
    )
    (net (code "56") (name "OUTB") (class "Default")
      (node (ref "R10") (pin "1") (pinfunction "1_1") (pintype "passive"))
      (node (ref "U$1") (pin "2") (pinfunction "OUTB_2") (pintype "bidirectional"))
    )
    (net (code "57") (name "OUTC") (class "Default")
      (node (ref "R13") (pin "1") (pinfunction "1_1") (pintype "passive"))
      (node (ref "U$1") (pin "7") (pinfunction "OUTC_7") (pintype "bidirectional"))
    )
    (net (code "58") (name "OUTD") (class "Default")
      (node (ref "R16") (pin "1") (pinfunction "1_1") (pintype "passive"))
      (node (ref "U$1") (pin "8") (pinfunction "OUTD_8") (pintype "bidirectional"))
    )
    (net (code "59") (name "REF_BIAS") (class "Default")
      (node (ref "IC2") (pin "3") (pinfunction "+IN_3") (pintype "input"))
      (node (ref "IC2") (pin "5") (pinfunction "+IN_5") (pintype "input"))
      (node (ref "IC3") (pin "3") (pinfunction "+IN_3") (pintype "input"))
      (node (ref "IC3") (pin "5") (pinfunction "+IN_5") (pintype "input"))
      (node (ref "R18") (pin "1") (pinfunction "1_1") (pintype "passive"))
      (node (ref "R19") (pin "2") (pinfunction "2_2") (pintype "passive"))
    )
    (net (code "60") (name "RESET") (class "Default")
      (node (ref "C8") (pin "1") (pinfunction "1_1") (pintype "passive"))
      (node (ref "R17") (pin "1") (pinfunction "1_1") (pintype "passive"))
      (node (ref "SV2") (pin "4") (pinfunction "4_4") (pintype "passive"))
      (node (ref "U1") (pin "7") (pinfunction "NRST_7") (pintype "bidirectional"))
    )
    (net (code "61") (name "SPI_LDAC") (class "Default")
      (node (ref "U$1") (pin "16") (pinfunction "LDAC_16") (pintype "bidirectional"))
      (node (ref "U1") (pin "26") (pinfunction "PB14_26") (pintype "bidirectional"))
    )
    (net (code "62") (name "SPI_MOSI") (class "Default")
      (node (ref "U$1") (pin "11") (pinfunction "DIN_11") (pintype "bidirectional"))
      (node (ref "U1") (pin "27") (pinfunction "PB15_27") (pintype "bidirectional"))
    )
    (net (code "63") (name "SPI_SCK") (class "Default")
      (node (ref "U$1") (pin "10") (pinfunction "SCLK_10") (pintype "bidirectional"))
      (node (ref "U1") (pin "28") (pinfunction "PD8_28") (pintype "bidirectional"))
    )
    (net (code "64") (name "SPI_SYNC") (class "Default")
      (node (ref "U$1") (pin "9") (pinfunction "__SYNC_9") (pintype "bidirectional"))
      (node (ref "U1") (pin "29") (pinfunction "PA8_29") (pintype "bidirectional"))
    )
    (net (code "65") (name "SWCLK") (class "Default")
      (node (ref "SV2") (pin "3") (pinfunction "3_3") (pintype "passive"))
      (node (ref "U1") (pin "37") (pinfunction "PA14_37") (pintype "bidirectional"))
    )
    (net (code "66") (name "SWDIO") (class "Default")
      (node (ref "SV2") (pin "2") (pinfunction "2_2") (pintype "passive"))
      (node (ref "U1") (pin "34") (pinfunction "PA13_34") (pintype "bidirectional"))
    )
    (net (code "67") (name "USB_DM") (class "Default")
      (node (ref "R29") (pin "2") (pinfunction "2_2") (pintype "passive"))
      (node (ref "U1") (pin "32") (pinfunction "PA11_32") (pintype "bidirectional"))
    )
    (net (code "68") (name "USB_DP") (class "Default")
      (node (ref "R28") (pin "2") (pinfunction "2_2") (pintype "passive"))
      (node (ref "R30") (pin "1") (pinfunction "1_1") (pintype "passive"))
      (node (ref "U1") (pin "33") (pinfunction "PA12_33") (pintype "bidirectional"))
    )
    (net (code "69") (name "VCCIO") (class "Default")
      (node (ref "C15") (pin "1") (pinfunction "1_1") (pintype "passive"))
      (node (ref "C16") (pin "1") (pinfunction "1_1") (pintype "passive"))
      (node (ref "C17") (pin "1") (pinfunction "1_1") (pintype "passive"))
      (node (ref "C18") (pin "1") (pinfunction "1_1") (pintype "passive"))
      (node (ref "C25") (pin "1") (pinfunction "1_1") (pintype "passive"))
      (node (ref "C3") (pin "1") (pinfunction "1_1") (pintype "passive"))
      (node (ref "R17") (pin "2") (pinfunction "2_2") (pintype "passive"))
      (node (ref "R30") (pin "2") (pinfunction "2_2") (pintype "passive"))
      (node (ref "U$1") (pin "12") (pinfunction "DVDD_12") (pintype "bidirectional"))
      (node (ref "U$1") (pin "13") (pinfunction "__RST_13") (pintype "bidirectional"))
      (node (ref "U$2") (pin "1") (pinfunction "VOUT_1") (pintype "bidirectional"))
      (node (ref "U1") (pin "1") (pinfunction "VBAT_1") (pintype "bidirectional"))
      (node (ref "U1") (pin "17") (pinfunction "VDD2_17") (pintype "bidirectional"))
      (node (ref "U1") (pin "24") (pinfunction "VDDSD_24") (pintype "bidirectional"))
      (node (ref "U1") (pin "25") (pinfunction "VDDREF_25") (pintype "bidirectional"))
      (node (ref "U1") (pin "48") (pinfunction "VDD1_48") (pintype "bidirectional"))
      (node (ref "U1") (pin "9") (pinfunction "VDDA_9") (pintype "bidirectional"))
    )
    (net (code "70") (name "unconnected-(J1-VBUS-Pad1)") (class "Default")
      (node (ref "J1") (pin "1") (pinfunction "VBUS_1") (pintype "bidirectional"))
    )
    (net (code "71") (name "unconnected-(JCK1-SWITCH-PadP$2_SWITCH)") (class "Default")
      (node (ref "JCK1") (pin "P$2_SWITCH") (pinfunction "SWITCH_P$2_SWITCH") (pintype "passive"))
    )
    (net (code "72") (name "unconnected-(JCK2-SWITCH-PadP$2_SWITCH)") (class "Default")
      (node (ref "JCK2") (pin "P$2_SWITCH") (pinfunction "SWITCH_P$2_SWITCH") (pintype "passive"))
    )
    (net (code "73") (name "unconnected-(JCK3-SWITCH-PadP$2_SWITCH)") (class "Default")
      (node (ref "JCK3") (pin "P$2_SWITCH") (pinfunction "SWITCH_P$2_SWITCH") (pintype "passive"))
    )
    (net (code "74") (name "unconnected-(JCK4-SWITCH-PadP$2_SWITCH)") (class "Default")
      (node (ref "JCK4") (pin "P$2_SWITCH") (pinfunction "SWITCH_P$2_SWITCH") (pintype "passive"))
    )
    (net (code "75") (name "unconnected-(JCK5-SWITCH-PadP$2_SWITCH)") (class "Default")
      (node (ref "JCK5") (pin "P$2_SWITCH") (pinfunction "SWITCH_P$2_SWITCH") (pintype "passive"))
    )
    (net (code "76") (name "unconnected-(JCK6-SWITCH-PadP$2_SWITCH)") (class "Default")
      (node (ref "JCK6") (pin "P$2_SWITCH") (pinfunction "SWITCH_P$2_SWITCH") (pintype "passive"))
    )
    (net (code "77") (name "unconnected-(JCK7-SWITCH-PadP$2_SWITCH)") (class "Default")
      (node (ref "JCK7") (pin "P$2_SWITCH") (pinfunction "SWITCH_P$2_SWITCH") (pintype "passive"))
    )
    (net (code "78") (name "unconnected-(JCK8-SWITCH-PadP$2_SWITCH)") (class "Default")
      (node (ref "JCK8") (pin "P$2_SWITCH") (pinfunction "SWITCH_P$2_SWITCH") (pintype "passive"))
    )
    (net (code "79") (name "unconnected-(U1-PA0-Pad10)") (class "Default")
      (node (ref "U1") (pin "10") (pinfunction "PA0_10") (pintype "bidirectional"))
    )
    (net (code "80") (name "unconnected-(U1-PA9-Pad30)") (class "Default")
      (node (ref "U1") (pin "30") (pinfunction "PA9_30") (pintype "bidirectional"))
    )
    (net (code "81") (name "unconnected-(U1-PA10-Pad31)") (class "Default")
      (node (ref "U1") (pin "31") (pinfunction "PA10_31") (pintype "bidirectional"))
    )
    (net (code "82") (name "unconnected-(U1-PA15-Pad38)") (class "Default")
      (node (ref "U1") (pin "38") (pinfunction "PA15_38") (pintype "bidirectional"))
    )
    (net (code "83") (name "unconnected-(U1-PB2-Pad20)") (class "Default")
      (node (ref "U1") (pin "20") (pinfunction "PB2_20") (pintype "bidirectional"))
    )
    (net (code "84") (name "unconnected-(U1-PB3-Pad39)") (class "Default")
      (node (ref "U1") (pin "39") (pinfunction "PB3_39") (pintype "bidirectional"))
    )
    (net (code "85") (name "unconnected-(U1-PB4-Pad40)") (class "Default")
      (node (ref "U1") (pin "40") (pinfunction "PB4_40") (pintype "bidirectional"))
    )
    (net (code "86") (name "unconnected-(U1-PB5-Pad41)") (class "Default")
      (node (ref "U1") (pin "41") (pinfunction "PB5_41") (pintype "bidirectional"))
    )
    (net (code "87") (name "unconnected-(U1-PC13-Pad2)") (class "Default")
      (node (ref "U1") (pin "2") (pinfunction "PC13_2") (pintype "bidirectional"))
    )
    (net (code "88") (name "unconnected-(U1-PC14-Pad3)") (class "Default")
      (node (ref "U1") (pin "3") (pinfunction "PC14_3") (pintype "bidirectional"))
    )
    (net (code "89") (name "unconnected-(U1-PC15-Pad4)") (class "Default")
      (node (ref "U1") (pin "4") (pinfunction "PC15_4") (pintype "bidirectional"))
    )
    (net (code "90") (name "unconnected-(U1-PE8-Pad21)") (class "Default")
      (node (ref "U1") (pin "21") (pinfunction "PE8_21") (pintype "bidirectional"))
    )
    (net (code "91") (name "unconnected-(U1-PE9-Pad22)") (class "Default")
      (node (ref "U1") (pin "22") (pinfunction "PE9_22") (pintype "bidirectional"))
    )
    (net (code "92") (name "unconnected-(U1-PF6-Pad35)") (class "Default")
      (node (ref "U1") (pin "35") (pinfunction "PF6_35") (pintype "bidirectional"))
    )
    (net (code "93") (name "unconnected-(U1-PF7-Pad36)") (class "Default")
      (node (ref "U1") (pin "36") (pinfunction "PF7_36") (pintype "bidirectional"))
    )
  )
)
